# Hexapod_REV1.net
KiCad netlist of a schematic drawn in EAGLE
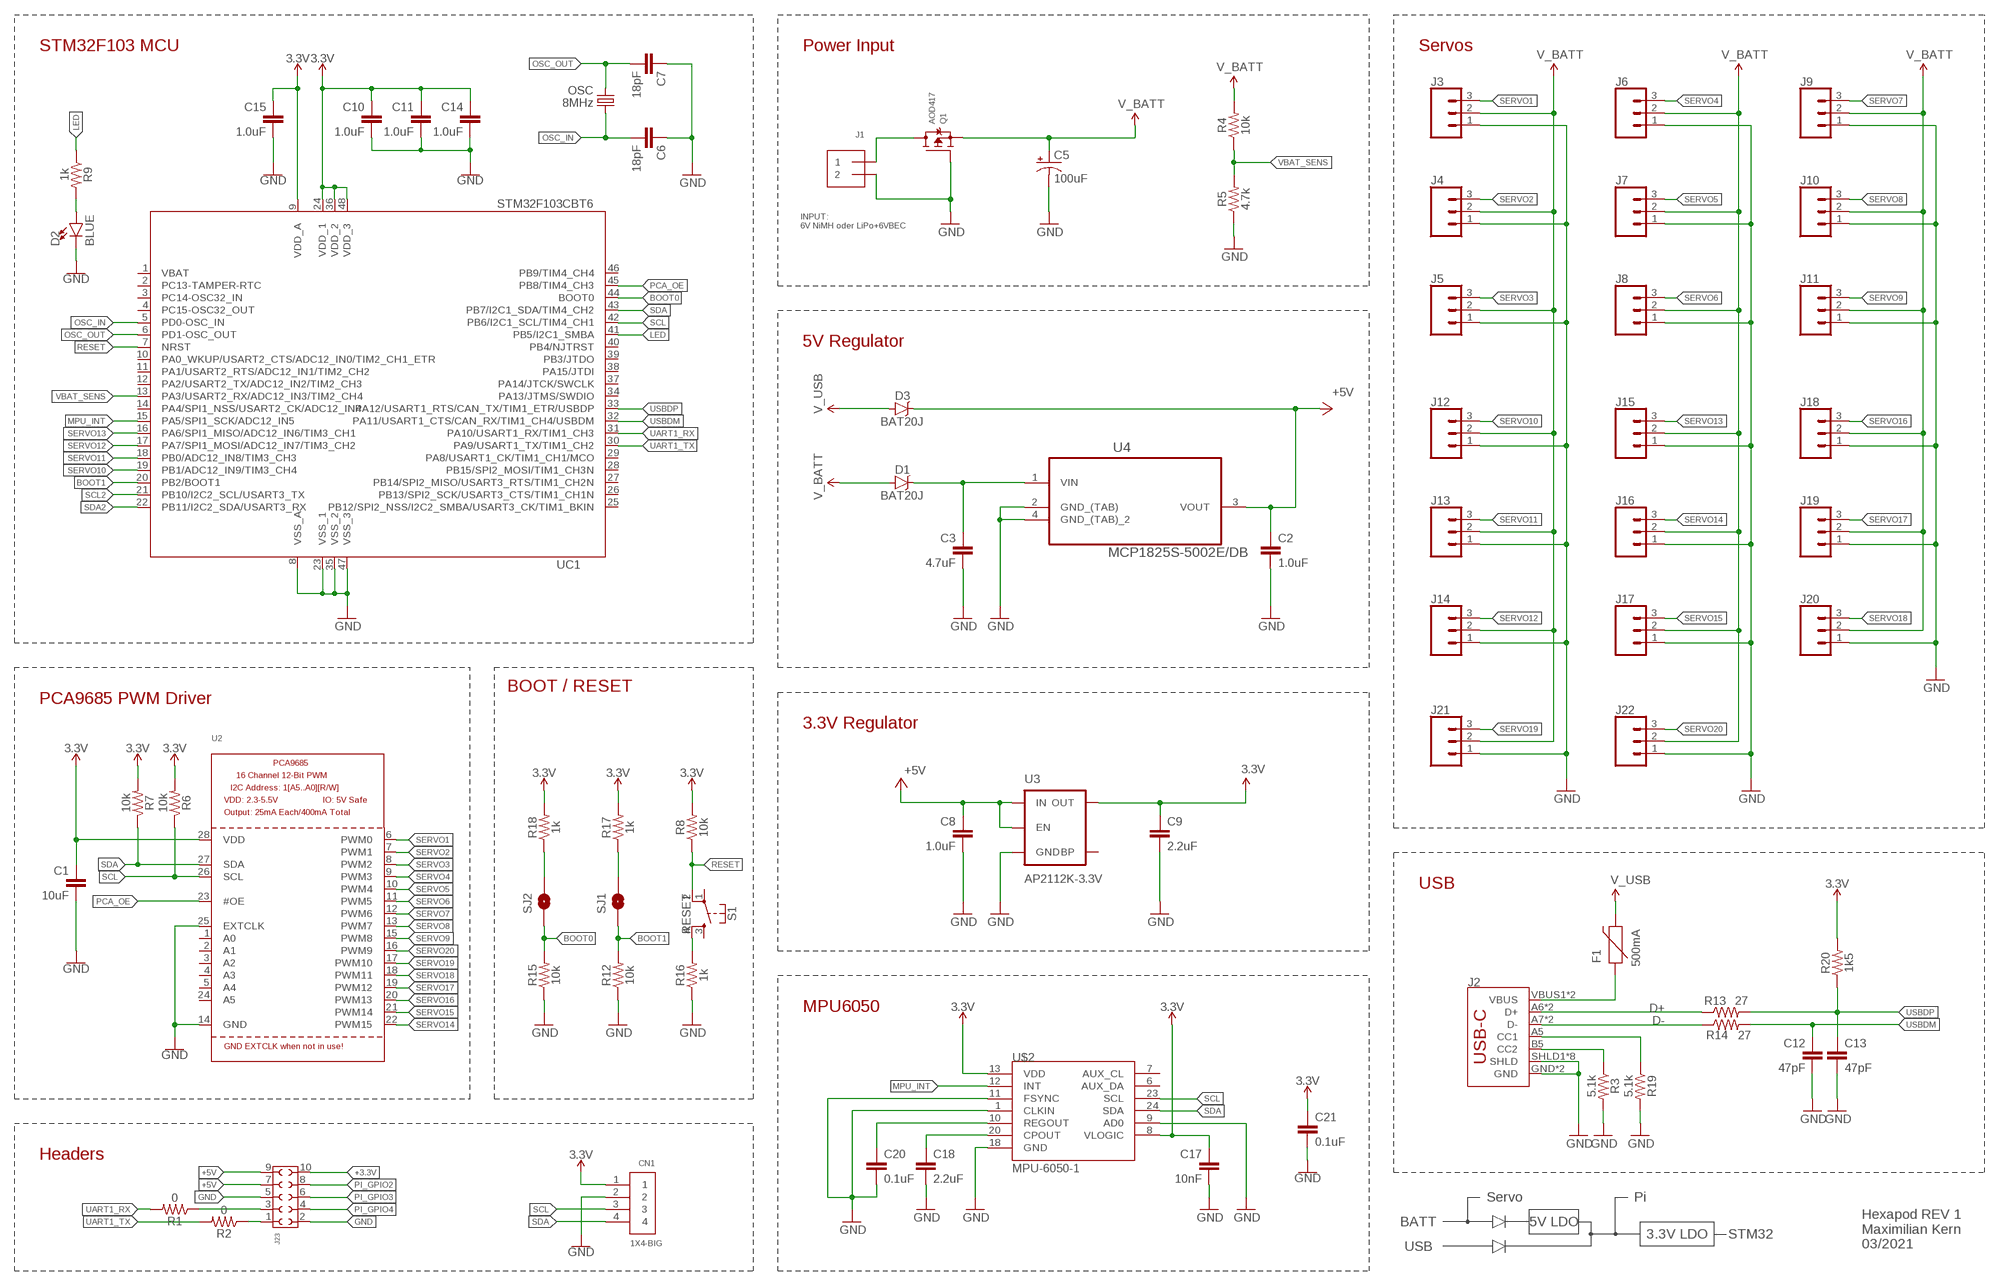
[diagram p0: schematic, sheet 1]

(export (version "E")
  (design (tool "Eeschema 10.0.6"))
  (components
    (comp (ref "C1")
      (value "10uF")
      (footprint "eagle-import:0805")
      (libsource (lib "eagle-import") (part "1.0UF-0805-25V-(+80/-20%)"))
    )
    (comp (ref "C2")
      (value "1.0uF")
      (footprint "eagle-import:0805")
      (libsource (lib "eagle-import") (part "1.0UF-0805-25V-(+80/-20%)"))
    )
    (comp (ref "C3")
      (value "4.7uF")
      (footprint "eagle-import:0805")
      (libsource (lib "eagle-import") (part "1.0UF-0805-25V-(+80/-20%)"))
    )
    (comp (ref "C5")
      (value "100uF")
      (footprint "eagle-import:PANASONIC_D")
      (libsource (lib "eagle-import") (part "100UF-POLAR-25V-20%(ELEC)"))
    )
    (comp (ref "C6")
      (value "18pF")
      (footprint "eagle-import:0603")
      (libsource (lib "eagle-import") (part "47PF-0603-50V-5%"))
    )
    (comp (ref "C7")
      (value "18pF")
      (footprint "eagle-import:0603")
      (libsource (lib "eagle-import") (part "47PF-0603-50V-5%"))
    )
    (comp (ref "C8")
      (value "1.0uF")
      (footprint "eagle-import:0805")
      (libsource (lib "eagle-import") (part "1.0UF-0805-25V-(+80/-20%)"))
    )
    (comp (ref "C9")
      (value "2.2uF")
      (footprint "eagle-import:0805")
      (libsource (lib "eagle-import") (part "1.0UF-0805-25V-(+80/-20%)"))
    )
    (comp (ref "C10")
      (value "1.0uF")
      (footprint "eagle-import:0805")
      (libsource (lib "eagle-import") (part "1.0UF-0805-25V-(+80/-20%)"))
    )
    (comp (ref "C11")
      (value "1.0uF")
      (footprint "eagle-import:0805")
      (libsource (lib "eagle-import") (part "1.0UF-0805-25V-(+80/-20%)"))
    )
    (comp (ref "C12")
      (value "47pF")
      (footprint "eagle-import:0603")
      (libsource (lib "eagle-import") (part "47PF-0603-50V-5%"))
    )
    (comp (ref "C13")
      (value "47pF")
      (footprint "eagle-import:0603")
      (libsource (lib "eagle-import") (part "47PF-0603-50V-5%"))
    )
    (comp (ref "C14")
      (value "1.0uF")
      (footprint "eagle-import:0805")
      (libsource (lib "eagle-import") (part "1.0UF-0805-25V-(+80/-20%)"))
    )
    (comp (ref "C15")
      (value "1.0uF")
      (footprint "eagle-import:0805")
      (libsource (lib "eagle-import") (part "1.0UF-0805-25V-(+80/-20%)"))
    )
    (comp (ref "C17")
      (value "10nF")
      (footprint "eagle-import:0603")
      (libsource (lib "eagle-import") (part "47PF-0603-50V-5%"))
    )
    (comp (ref "C18")
      (value "2.2uF")
      (footprint "eagle-import:0805")
      (libsource (lib "eagle-import") (part "1.0UF-0805-25V-(+80/-20%)"))
    )
    (comp (ref "C20")
      (value "0.1uF")
      (footprint "eagle-import:0603")
      (libsource (lib "eagle-import") (part "0.1UF-0603-25V-(+80/-20%)"))
    )
    (comp (ref "C21")
      (value "0.1uF")
      (footprint "eagle-import:0603")
      (libsource (lib "eagle-import") (part "0.1UF-0603-25V-(+80/-20%)"))
    )
    (comp (ref "CN1")
      (value "1X4-BIG")
      (footprint "eagle-import:1X04-BIG")
      (libsource (lib "eagle-import") (part "1X4-BIG"))
    )
    (comp (ref "D1")
      (value "BAT20J")
      (footprint "eagle-import:SOD-323")
      (libsource (lib "eagle-import") (part "DIODE-SCHOTTKY-BAT20J"))
    )
    (comp (ref "D2")
      (value "BLUE")
      (footprint "eagle-import:LED-0603@2")
      (libsource (lib "eagle-import") (part "LED-BLUE0603"))
    )
    (comp (ref "D3")
      (value "BAT20J")
      (footprint "eagle-import:SOD-323")
      (libsource (lib "eagle-import") (part "DIODE-SCHOTTKY-BAT20J"))
    )
    (comp (ref "F1")
      (value "500mA")
      (footprint "eagle-import:PTC-1206")
      (libsource (lib "eagle-import") (part "PTCSMD"))
    )
    (comp (ref "J1")
      (value "TERMBLOCK_1X2")
      (footprint "eagle-import:TERMBLOCK_1X2-3.5MM")
      (libsource (lib "eagle-import") (part "TERMBLOCK_1X2"))
    )
    (comp (ref "J2")
      (value "USB_C16PIN")
      (footprint "eagle-import:USB-C-16P")
      (libsource (lib "eagle-import") (part "USB_C16PIN"))
    )
    (comp (ref "J3")
      (value "CONN_03")
      (footprint "eagle-import:1X03")
      (libsource (lib "eagle-import") (part "CONN_03"))
    )
    (comp (ref "J4")
      (value "CONN_03")
      (footprint "eagle-import:1X03")
      (libsource (lib "eagle-import") (part "CONN_03"))
    )
    (comp (ref "J5")
      (value "CONN_03")
      (footprint "eagle-import:1X03")
      (libsource (lib "eagle-import") (part "CONN_03"))
    )
    (comp (ref "J6")
      (value "CONN_03")
      (footprint "eagle-import:1X03")
      (libsource (lib "eagle-import") (part "CONN_03"))
    )
    (comp (ref "J7")
      (value "CONN_03")
      (footprint "eagle-import:1X03")
      (libsource (lib "eagle-import") (part "CONN_03"))
    )
    (comp (ref "J8")
      (value "CONN_03")
      (footprint "eagle-import:1X03")
      (libsource (lib "eagle-import") (part "CONN_03"))
    )
    (comp (ref "J9")
      (value "CONN_03")
      (footprint "eagle-import:1X03")
      (libsource (lib "eagle-import") (part "CONN_03"))
    )
    (comp (ref "J10")
      (value "CONN_03")
      (footprint "eagle-import:1X03")
      (libsource (lib "eagle-import") (part "CONN_03"))
    )
    (comp (ref "J11")
      (value "CONN_03")
      (footprint "eagle-import:1X03")
      (libsource (lib "eagle-import") (part "CONN_03"))
    )
    (comp (ref "J12")
      (value "CONN_03")
      (footprint "eagle-import:1X03")
      (libsource (lib "eagle-import") (part "CONN_03"))
    )
    (comp (ref "J13")
      (value "CONN_03")
      (footprint "eagle-import:1X03")
      (libsource (lib "eagle-import") (part "CONN_03"))
    )
    (comp (ref "J14")
      (value "CONN_03")
      (footprint "eagle-import:1X03")
      (libsource (lib "eagle-import") (part "CONN_03"))
    )
    (comp (ref "J15")
      (value "CONN_03")
      (footprint "eagle-import:1X03")
      (libsource (lib "eagle-import") (part "CONN_03"))
    )
    (comp (ref "J16")
      (value "CONN_03")
      (footprint "eagle-import:1X03")
      (libsource (lib "eagle-import") (part "CONN_03"))
    )
    (comp (ref "J17")
      (value "CONN_03")
      (footprint "eagle-import:1X03")
      (libsource (lib "eagle-import") (part "CONN_03"))
    )
    (comp (ref "J18")
      (value "CONN_03")
      (footprint "eagle-import:1X03")
      (libsource (lib "eagle-import") (part "CONN_03"))
    )
    (comp (ref "J19")
      (value "CONN_03")
      (footprint "eagle-import:1X03")
      (libsource (lib "eagle-import") (part "CONN_03"))
    )
    (comp (ref "J20")
      (value "CONN_03")
      (footprint "eagle-import:1X03")
      (libsource (lib "eagle-import") (part "CONN_03"))
    )
    (comp (ref "J21")
      (value "CONN_03")
      (footprint "eagle-import:1X03")
      (libsource (lib "eagle-import") (part "CONN_03"))
    )
    (comp (ref "J22")
      (value "CONN_03")
      (footprint "eagle-import:1X03")
      (libsource (lib "eagle-import") (part "CONN_03"))
    )
    (comp (ref "J23")
      (value "6103XX21821_61031021821")
      (footprint "eagle-import:61031021821")
      (libsource (lib "eagle-import") (part "6103XX21821_61031021821"))
    )
    (comp (ref "OSC")
      (value "8MHz")
      (footprint "eagle-import:CRYSTAL-SMD-5X3")
      (libsource (lib "eagle-import") (part "CRYSTAL5X3"))
    )
    (comp (ref "Q1")
      (value "AOD417")
      (footprint "eagle-import:TO252")
      (libsource (lib "eagle-import") (part "MOSFET-PTO252"))
    )
    (comp (ref "R1")
      (value "0")
      (footprint "eagle-import:0603")
      (libsource (lib "eagle-import") (part "10KOHM-0603-1/10W-1%"))
    )
    (comp (ref "R2")
      (value "0")
      (footprint "eagle-import:0603")
      (libsource (lib "eagle-import") (part "10KOHM-0603-1/10W-1%"))
    )
    (comp (ref "R3")
      (value "5.1k")
      (footprint "eagle-import:0603")
      (libsource (lib "eagle-import") (part "10KOHM-0603-1/10W-1%"))
    )
    (comp (ref "R4")
      (value "10k")
      (footprint "eagle-import:0603")
      (libsource (lib "eagle-import") (part "10KOHM-0603-1/10W-1%"))
    )
    (comp (ref "R5")
      (value "4.7k")
      (footprint "eagle-import:0603")
      (libsource (lib "eagle-import") (part "10KOHM-0603-1/10W-1%"))
    )
    (comp (ref "R6")
      (value "10k")
      (footprint "eagle-import:0603")
      (libsource (lib "eagle-import") (part "10KOHM-0603-1/10W-1%"))
    )
    (comp (ref "R7")
      (value "10k")
      (footprint "eagle-import:0603")
      (libsource (lib "eagle-import") (part "10KOHM-0603-1/10W-1%"))
    )
    (comp (ref "R8")
      (value "10k")
      (footprint "eagle-import:0603")
      (libsource (lib "eagle-import") (part "10KOHM-0603-1/10W-1%"))
    )
    (comp (ref "R9")
      (value "1k")
      (footprint "eagle-import:0603")
      (libsource (lib "eagle-import") (part "1KOHM-0603-1/10W-1%"))
    )
    (comp (ref "R12")
      (value "10k")
      (footprint "eagle-import:0603")
      (libsource (lib "eagle-import") (part "10KOHM-0603-1/10W-1%"))
    )
    (comp (ref "R13")
      (value "27")
      (footprint "eagle-import:0603")
      (libsource (lib "eagle-import") (part "27OHM1/10W1%(0603)0603-RES"))
    )
    (comp (ref "R14")
      (value "27")
      (footprint "eagle-import:0603")
      (libsource (lib "eagle-import") (part "27OHM1/10W1%(0603)0603-RES"))
    )
    (comp (ref "R15")
      (value "10k")
      (footprint "eagle-import:0603")
      (libsource (lib "eagle-import") (part "10KOHM-0603-1/10W-1%"))
    )
    (comp (ref "R16")
      (value "1k")
      (footprint "eagle-import:0603")
      (libsource (lib "eagle-import") (part "10KOHM-0603-1/10W-1%"))
    )
    (comp (ref "R17")
      (value "1k")
      (footprint "eagle-import:0603")
      (libsource (lib "eagle-import") (part "10KOHM-0603-1/10W-1%"))
    )
    (comp (ref "R18")
      (value "1k")
      (footprint "eagle-import:0603")
      (libsource (lib "eagle-import") (part "10KOHM-0603-1/10W-1%"))
    )
    (comp (ref "R19")
      (value "5.1k")
      (footprint "eagle-import:0603")
      (libsource (lib "eagle-import") (part "10KOHM-0603-1/10W-1%"))
    )
    (comp (ref "R20")
      (value "1k5")
      (footprint "eagle-import:0603")
      (libsource (lib "eagle-import") (part "10KOHM-0603-1/10W-1%"))
    )
    (comp (ref "S1")
      (value "RESET")
      (footprint "eagle-import:TACTILE_SWITCH_SMD_4.6X2.8MM")
      (libsource (lib "eagle-import") (part "MOMENTARY-SWITCH-SPST-2-SMD-4.6X2.8MM"))
    )
    (comp (ref "SJ1")
      (value "JUMPER-PAD-2-NOYES_SILK")
      (footprint "eagle-import:PAD-JUMPER-2-NO_YES_SILK")
      (libsource (lib "eagle-import") (part "JUMPER-PAD-2-NOYES_SILK"))
    )
    (comp (ref "SJ2")
      (value "JUMPER-PAD-2-NOYES_SILK")
      (footprint "eagle-import:PAD-JUMPER-2-NO_YES_SILK")
      (libsource (lib "eagle-import") (part "JUMPER-PAD-2-NOYES_SILK"))
    )
    (comp (ref "U$2")
      (value "MPU-6050-1")
      (footprint "eagle-import:QFN-24-4MM2")
      (libsource (lib "eagle-import") (part "MPU-6050-1"))
    )
    (comp (ref "U2")
      (value "PCA9685")
      (footprint "eagle-import:TSSOP28")
      (libsource (lib "eagle-import") (part "PCA9685"))
    )
    (comp (ref "U3")
      (value "AP2112K-3.3V")
      (footprint "eagle-import:SOT23-5")
      (libsource (lib "eagle-import") (part "V_REG_LDOSMD"))
    )
    (comp (ref "U4")
      (value "MCP1825S-5002E/DB")
      (footprint "eagle-import:SOT230P700X180-4N")
      (libsource (lib "eagle-import") (part "MCP1825S-5002E/DB"))
    )
    (comp (ref "UC1")
      (value "STM32F103CBT6")
      (footprint "eagle-import:LQFP48")
      (libsource (lib "eagle-import") (part "STM32F103CB"))
    )
  )
  (nets
    (net (code "1") (name "+3.3V") (class "Default")
      (node (ref "J23") (pin "10") (pinfunction "10_10") (pintype "passive"))
    )
    (net (code "2") (name "+5V") (class "Default")
      (node (ref "C2") (pin "1") (pinfunction "1_1") (pintype "passive"))
      (node (ref "C8") (pin "1") (pinfunction "1_1") (pintype "passive"))
      (node (ref "D3") (pin "C") (pinfunction "C_C") (pintype "passive"))
      (node (ref "J23") (pin "7") (pinfunction "7_7") (pintype "passive"))
      (node (ref "J23") (pin "9") (pinfunction "9_9") (pintype "passive"))
      (node (ref "U3") (pin "1") (pinfunction "IN_1") (pintype "input"))
      (node (ref "U3") (pin "3") (pinfunction "EN_3") (pintype "input"))
      (node (ref "U4") (pin "3") (pinfunction "VOUT_3") (pintype "output"))
    )
    (net (code "3") (name "/D+") (class "Default")
      (node (ref "J2") (pin "A6") (pinfunction "D+_A6") (pintype "bidirectional"))
      (node (ref "J2") (pin "B6") (pinfunction "D+_B6") (pintype "bidirectional"))
      (node (ref "R13") (pin "1") (pinfunction "1_1") (pintype "passive"))
    )
    (net (code "4") (name "/D-") (class "Default")
      (node (ref "J2") (pin "A7") (pinfunction "D-_A7") (pintype "bidirectional"))
      (node (ref "J2") (pin "B7") (pinfunction "D-_B7") (pintype "bidirectional"))
      (node (ref "R14") (pin "1") (pinfunction "1_1") (pintype "passive"))
    )
    (net (code "5") (name "/PI_TXD") (class "Default")
      (node (ref "J23") (pin "3") (pinfunction "3_3") (pintype "passive"))
      (node (ref "R1") (pin "1") (pinfunction "1_1") (pintype "passive"))
    )
    (net (code "6") (name "/VBAT") (class "Default")
      (node (ref "UC1") (pin "1") (pinfunction "VBAT_1") (pintype "power_in"))
    )
    (net (code "7") (name "3.3V") (class "Default")
      (node (ref "C1") (pin "1") (pinfunction "1_1") (pintype "passive"))
      (node (ref "C10") (pin "1") (pinfunction "1_1") (pintype "passive"))
      (node (ref "C11") (pin "1") (pinfunction "1_1") (pintype "passive"))
      (node (ref "C14") (pin "1") (pinfunction "1_1") (pintype "passive"))
      (node (ref "C15") (pin "1") (pinfunction "1_1") (pintype "passive"))
      (node (ref "C17") (pin "1") (pinfunction "1_1") (pintype "passive"))
      (node (ref "C21") (pin "1") (pinfunction "1_1") (pintype "passive"))
      (node (ref "C9") (pin "1") (pinfunction "1_1") (pintype "passive"))
      (node (ref "CN1") (pin "1") (pinfunction "1_1") (pintype "bidirectional"))
      (node (ref "R17") (pin "2") (pinfunction "2_2") (pintype "passive"))
      (node (ref "R18") (pin "2") (pinfunction "2_2") (pintype "passive"))
      (node (ref "R20") (pin "2") (pinfunction "2_2") (pintype "passive"))
      (node (ref "R6") (pin "2") (pinfunction "2_2") (pintype "passive"))
      (node (ref "R7") (pin "2") (pinfunction "2_2") (pintype "passive"))
      (node (ref "R8") (pin "2") (pinfunction "2_2") (pintype "passive"))
      (node (ref "U$2") (pin "13") (pinfunction "VDD_13") (pintype "bidirectional"))
      (node (ref "U$2") (pin "8") (pinfunction "VLOGIC_8") (pintype "bidirectional"))
      (node (ref "U2") (pin "28") (pinfunction "VDD_28") (pintype "power_in"))
      (node (ref "U3") (pin "5") (pinfunction "OUT_5") (pintype "passive"))
      (node (ref "UC1") (pin "24") (pinfunction "VDD_1_24") (pintype "power_in"))
      (node (ref "UC1") (pin "36") (pinfunction "VDD_2_36") (pintype "power_in"))
      (node (ref "UC1") (pin "48") (pinfunction "VDD_3_48") (pintype "power_in"))
      (node (ref "UC1") (pin "9") (pinfunction "VDD_A_9") (pintype "power_in"))
    )
    (net (code "8") (name "BOOT0") (class "Default")
      (node (ref "R15") (pin "2") (pinfunction "2_2") (pintype "passive"))
      (node (ref "SJ2") (pin "1") (pinfunction "1_1") (pintype "passive"))
      (node (ref "UC1") (pin "44") (pinfunction "BOOT0_44") (pintype "input"))
    )
    (net (code "9") (name "BOOT1") (class "Default")
      (node (ref "R12") (pin "2") (pinfunction "2_2") (pintype "passive"))
      (node (ref "SJ1") (pin "1") (pinfunction "1_1") (pintype "passive"))
      (node (ref "UC1") (pin "20") (pinfunction "PB2/BOOT1_20") (pintype "bidirectional"))
    )
    (net (code "10") (name "GND") (class "Default")
      (node (ref "C1") (pin "2") (pinfunction "2_2") (pintype "passive"))
      (node (ref "C10") (pin "2") (pinfunction "2_2") (pintype "passive"))
      (node (ref "C11") (pin "2") (pinfunction "2_2") (pintype "passive"))
      (node (ref "C12") (pin "2") (pinfunction "2_2") (pintype "passive"))
      (node (ref "C13") (pin "2") (pinfunction "2_2") (pintype "passive"))
      (node (ref "C14") (pin "2") (pinfunction "2_2") (pintype "passive"))
      (node (ref "C15") (pin "2") (pinfunction "2_2") (pintype "passive"))
      (node (ref "C17") (pin "2") (pinfunction "2_2") (pintype "passive"))
      (node (ref "C18") (pin "2") (pinfunction "2_2") (pintype "passive"))
      (node (ref "C2") (pin "2") (pinfunction "2_2") (pintype "passive"))
      (node (ref "C20") (pin "2") (pinfunction "2_2") (pintype "passive"))
      (node (ref "C21") (pin "2") (pinfunction "2_2") (pintype "passive"))
      (node (ref "C3") (pin "2") (pinfunction "2_2") (pintype "passive"))
      (node (ref "C5") (pin "-") (pinfunction "-_-") (pintype "passive"))
      (node (ref "C6") (pin "1") (pinfunction "1_1") (pintype "passive"))
      (node (ref "C7") (pin "1") (pinfunction "1_1") (pintype "passive"))
      (node (ref "C8") (pin "2") (pinfunction "2_2") (pintype "passive"))
      (node (ref "C9") (pin "2") (pinfunction "2_2") (pintype "passive"))
      (node (ref "CN1") (pin "2") (pinfunction "2_2") (pintype "bidirectional"))
      (node (ref "D2") (pin "C") (pinfunction "C_C") (pintype "passive"))
      (node (ref "J1") (pin "2") (pinfunction "2_2") (pintype "passive"))
      (node (ref "J10") (pin "1") (pinfunction "1_1") (pintype "passive"))
      (node (ref "J11") (pin "1") (pinfunction "1_1") (pintype "passive"))
      (node (ref "J12") (pin "1") (pinfunction "1_1") (pintype "passive"))
      (node (ref "J13") (pin "1") (pinfunction "1_1") (pintype "passive"))
      (node (ref "J14") (pin "1") (pinfunction "1_1") (pintype "passive"))
      (node (ref "J15") (pin "1") (pinfunction "1_1") (pintype "passive"))
      (node (ref "J16") (pin "1") (pinfunction "1_1") (pintype "passive"))
      (node (ref "J17") (pin "1") (pinfunction "1_1") (pintype "passive"))
      (node (ref "J18") (pin "1") (pinfunction "1_1") (pintype "passive"))
      (node (ref "J19") (pin "1") (pinfunction "1_1") (pintype "passive"))
      (node (ref "J2") (pin "GND") (pinfunction "GND_GND") (pintype "bidirectional"))
      (node (ref "J2") (pin "GND2") (pinfunction "GND_GND2") (pintype "bidirectional"))
      (node (ref "J2") (pin "SHLD1") (pinfunction "SHLD_SHLD1") (pintype "bidirectional"))
      (node (ref "J2") (pin "SHLD2") (pinfunction "SHLD_SHLD2") (pintype "bidirectional"))
      (node (ref "J2") (pin "SHLD3") (pinfunction "SHLD_SHLD3") (pintype "bidirectional"))
      (node (ref "J2") (pin "SHLD4") (pinfunction "SHLD_SHLD4") (pintype "bidirectional"))
      (node (ref "J2") (pin "SHLD5") (pinfunction "SHLD_SHLD5") (pintype "bidirectional"))
      (node (ref "J2") (pin "SHLD6") (pinfunction "SHLD_SHLD6") (pintype "bidirectional"))
      (node (ref "J2") (pin "SHLD7") (pinfunction "SHLD_SHLD7") (pintype "bidirectional"))
      (node (ref "J2") (pin "SHLD8") (pinfunction "SHLD_SHLD8") (pintype "bidirectional"))
      (node (ref "J20") (pin "1") (pinfunction "1_1") (pintype "passive"))
      (node (ref "J21") (pin "1") (pinfunction "1_1") (pintype "passive"))
      (node (ref "J22") (pin "1") (pinfunction "1_1") (pintype "passive"))
      (node (ref "J23") (pin "2") (pinfunction "2_2") (pintype "passive"))
      (node (ref "J23") (pin "5") (pinfunction "5_5") (pintype "passive"))
      (node (ref "J3") (pin "1") (pinfunction "1_1") (pintype "passive"))
      (node (ref "J4") (pin "1") (pinfunction "1_1") (pintype "passive"))
      (node (ref "J5") (pin "1") (pinfunction "1_1") (pintype "passive"))
      (node (ref "J6") (pin "1") (pinfunction "1_1") (pintype "passive"))
      (node (ref "J7") (pin "1") (pinfunction "1_1") (pintype "passive"))
      (node (ref "J8") (pin "1") (pinfunction "1_1") (pintype "passive"))
      (node (ref "J9") (pin "1") (pinfunction "1_1") (pintype "passive"))
      (node (ref "Q1") (pin "1") (pinfunction "G_1") (pintype "passive"))
      (node (ref "R12") (pin "1") (pinfunction "1_1") (pintype "passive"))
      (node (ref "R15") (pin "1") (pinfunction "1_1") (pintype "passive"))
      (node (ref "R16") (pin "1") (pinfunction "1_1") (pintype "passive"))
      (node (ref "R19") (pin "2") (pinfunction "2_2") (pintype "passive"))
      (node (ref "R3") (pin "2") (pinfunction "2_2") (pintype "passive"))
      (node (ref "R5") (pin "1") (pinfunction "1_1") (pintype "passive"))
      (node (ref "U$2") (pin "1") (pinfunction "CLKIN_1") (pintype "bidirectional"))
      (node (ref "U$2") (pin "11") (pinfunction "FSYNC_11") (pintype "bidirectional"))
      (node (ref "U$2") (pin "18") (pinfunction "GND_18") (pintype "bidirectional"))
      (node (ref "U$2") (pin "9") (pinfunction "AD0_9") (pintype "bidirectional"))
      (node (ref "U2") (pin "14") (pinfunction "GND_14") (pintype "power_in"))
      (node (ref "U2") (pin "25") (pinfunction "EXTCLK_25") (pintype "input"))
      (node (ref "U3") (pin "2") (pinfunction "GND_2") (pintype "input"))
      (node (ref "U4") (pin "2") (pinfunction "GND_(TAB)_2") (pintype "passive"))
      (node (ref "U4") (pin "4") (pinfunction "GND_(TAB)_2_4") (pintype "passive"))
      (node (ref "UC1") (pin "23") (pinfunction "VSS_1_23") (pintype "power_in"))
      (node (ref "UC1") (pin "35") (pinfunction "VSS_2_35") (pintype "power_in"))
      (node (ref "UC1") (pin "47") (pinfunction "VSS_3_47") (pintype "power_in"))
      (node (ref "UC1") (pin "8") (pinfunction "VSS_A_8") (pintype "power_in"))
    )
    (net (code "11") (name "LED") (class "Default")
      (node (ref "R9") (pin "1") (pinfunction "1_1") (pintype "passive"))
      (node (ref "UC1") (pin "41") (pinfunction "PB5/I2C1_SMBA_41") (pintype "input"))
    )
    (net (code "12") (name "MPU_INT") (class "Default")
      (node (ref "U$2") (pin "12") (pinfunction "INT_12") (pintype "bidirectional"))
      (node (ref "UC1") (pin "15") (pinfunction "PA5/SPI1_SCK/ADC12_IN5_15") (pintype "bidirectional"))
    )
    (net (code "13") (name "Net-(D2-PadA)") (class "Default")
      (node (ref "D2") (pin "A") (pinfunction "A_A") (pintype "passive"))
      (node (ref "R9") (pin "2") (pinfunction "2_2") (pintype "passive"))
    )
    (net (code "14") (name "Net-(F1-Pad1)") (class "Default")
      (node (ref "F1") (pin "1") (pinfunction "1_1") (pintype "bidirectional"))
      (node (ref "J2") (pin "VBUS1") (pinfunction "VBUS_VBUS1") (pintype "bidirectional"))
      (node (ref "J2") (pin "VBUS2") (pinfunction "VBUS_VBUS2") (pintype "bidirectional"))
    )
    (net (code "15") (name "Net-(J2-CC1)") (class "Default")
      (node (ref "J2") (pin "A5") (pinfunction "CC1_A5") (pintype "bidirectional"))
      (node (ref "R19") (pin "1") (pinfunction "1_1") (pintype "passive"))
    )
    (net (code "16") (name "Net-(J2-CC2)") (class "Default")
      (node (ref "J2") (pin "B5") (pinfunction "CC2_B5") (pintype "bidirectional"))
      (node (ref "R3") (pin "1") (pinfunction "1_1") (pintype "passive"))
    )
    (net (code "17") (name "Net-(J23-Pad1)") (class "Default")
      (node (ref "J23") (pin "1") (pinfunction "1_1") (pintype "passive"))
      (node (ref "R2") (pin "1") (pinfunction "1_1") (pintype "passive"))
    )
    (net (code "18") (name "Net-(Q1-D)") (class "Default")
      (node (ref "J1") (pin "1") (pinfunction "1_1") (pintype "passive"))
      (node (ref "Q1") (pin "3") (pinfunction "D_3") (pintype "passive"))
    )
    (net (code "19") (name "Net-(R16-Pad2)") (class "Default")
      (node (ref "R16") (pin "2") (pinfunction "2_2") (pintype "passive"))
      (node (ref "S1") (pin "4") (pinfunction "4_4") (pintype "passive"))
    )
    (net (code "20") (name "Net-(R17-Pad1)") (class "Default")
      (node (ref "R17") (pin "1") (pinfunction "1_1") (pintype "passive"))
      (node (ref "SJ1") (pin "2") (pinfunction "2_2") (pintype "passive"))
    )
    (net (code "21") (name "Net-(R18-Pad1)") (class "Default")
      (node (ref "R18") (pin "1") (pinfunction "1_1") (pintype "passive"))
      (node (ref "SJ2") (pin "2") (pinfunction "2_2") (pintype "passive"))
    )
    (net (code "22") (name "Net-(U$2-CPOUT)") (class "Default")
      (node (ref "C18") (pin "1") (pinfunction "1_1") (pintype "passive"))
      (node (ref "U$2") (pin "20") (pinfunction "CPOUT_20") (pintype "bidirectional"))
    )
    (net (code "23") (name "Net-(U$2-REGOUT)") (class "Default")
      (node (ref "C20") (pin "1") (pinfunction "1_1") (pintype "passive"))
      (node (ref "U$2") (pin "10") (pinfunction "REGOUT_10") (pintype "bidirectional"))
    )
    (net (code "24") (name "Net-(U4-VIN)") (class "Default")
      (node (ref "C3") (pin "1") (pinfunction "1_1") (pintype "passive"))
      (node (ref "D1") (pin "C") (pinfunction "C_C") (pintype "passive"))
      (node (ref "U4") (pin "1") (pinfunction "VIN_1") (pintype "input"))
    )
    (net (code "25") (name "OSC_IN") (class "Default")
      (node (ref "C6") (pin "2") (pinfunction "2_2") (pintype "passive"))
      (node (ref "OSC") (pin "1") (pinfunction "1_1") (pintype "passive"))
      (node (ref "UC1") (pin "5") (pinfunction "PD0-OSC_IN_5") (pintype "input"))
    )
    (net (code "26") (name "OSC_OUT") (class "Default")
      (node (ref "C7") (pin "2") (pinfunction "2_2") (pintype "passive"))
      (node (ref "OSC") (pin "3") (pinfunction "2_3") (pintype "passive"))
      (node (ref "UC1") (pin "6") (pinfunction "PD1-OSC_OUT_6") (pintype "input"))
    )
    (net (code "27") (name "PCA_OE") (class "Default")
      (node (ref "U2") (pin "23") (pinfunction "#OE_23") (pintype "input"))
      (node (ref "UC1") (pin "45") (pinfunction "PB8/TIM4_CH3_45") (pintype "bidirectional"))
    )
    (net (code "28") (name "PI_GPIO2") (class "Default")
      (node (ref "J23") (pin "8") (pinfunction "8_8") (pintype "passive"))
    )
    (net (code "29") (name "PI_GPIO3") (class "Default")
      (node (ref "J23") (pin "6") (pinfunction "6_6") (pintype "passive"))
    )
    (net (code "30") (name "PI_GPIO4") (class "Default")
      (node (ref "J23") (pin "4") (pinfunction "4_4") (pintype "passive"))
    )
    (net (code "31") (name "RESET") (class "Default")
      (node (ref "R8") (pin "1") (pinfunction "1_1") (pintype "passive"))
      (node (ref "S1") (pin "2") (pinfunction "2_2") (pintype "passive"))
      (node (ref "UC1") (pin "7") (pinfunction "NRST_7") (pintype "input"))
    )
    (net (code "32") (name "SCL") (class "Default")
      (node (ref "CN1") (pin "3") (pinfunction "3_3") (pintype "bidirectional"))
      (node (ref "R6") (pin "1") (pinfunction "1_1") (pintype "passive"))
      (node (ref "U$2") (pin "23") (pinfunction "SCL_23") (pintype "bidirectional"))
      (node (ref "U2") (pin "26") (pinfunction "SCL_26") (pintype "bidirectional"))
      (node (ref "UC1") (pin "42") (pinfunction "PB6/I2C1_SCL/TIM4_CH1_42") (pintype "input"))
    )
    (net (code "33") (name "SCL2") (class "Default")
      (node (ref "UC1") (pin "21") (pinfunction "PB10/I2C2_SCL/USART3_TX_21") (pintype "input"))
    )
    (net (code "34") (name "SDA") (class "Default")
      (node (ref "CN1") (pin "4") (pinfunction "4_4") (pintype "bidirectional"))
      (node (ref "R7") (pin "1") (pinfunction "1_1") (pintype "passive"))
      (node (ref "U$2") (pin "24") (pinfunction "SDA_24") (pintype "bidirectional"))
      (node (ref "U2") (pin "27") (pinfunction "SDA_27") (pintype "bidirectional"))
      (node (ref "UC1") (pin "43") (pinfunction "PB7/I2C1_SDA/TIM4_CH2_43") (pintype "bidirectional"))
    )
    (net (code "35") (name "SDA2") (class "Default")
      (node (ref "UC1") (pin "22") (pinfunction "PB11/I2C2_SDA/USART3_RX_22") (pintype "input"))
    )
    (net (code "36") (name "SERVO1") (class "Default")
      (node (ref "J3") (pin "3") (pinfunction "3_3") (pintype "passive"))
      (node (ref "U2") (pin "6") (pinfunction "PWM0_6") (pintype "output"))
    )
    (net (code "37") (name "SERVO2") (class "Default")
      (node (ref "J4") (pin "3") (pinfunction "3_3") (pintype "passive"))
      (node (ref "U2") (pin "7") (pinfunction "PWM1_7") (pintype "output"))
    )
    (net (code "38") (name "SERVO3") (class "Default")
      (node (ref "J5") (pin "3") (pinfunction "3_3") (pintype "passive"))
      (node (ref "U2") (pin "8") (pinfunction "PWM2_8") (pintype "output"))
    )
    (net (code "39") (name "SERVO4") (class "Default")
      (node (ref "J6") (pin "3") (pinfunction "3_3") (pintype "passive"))
      (node (ref "U2") (pin "9") (pinfunction "PWM3_9") (pintype "output"))
    )
    (net (code "40") (name "SERVO5") (class "Default")
      (node (ref "J7") (pin "3") (pinfunction "3_3") (pintype "passive"))
      (node (ref "U2") (pin "10") (pinfunction "PWM4_10") (pintype "output"))
    )
    (net (code "41") (name "SERVO6") (class "Default")
      (node (ref "J8") (pin "3") (pinfunction "3_3") (pintype "passive"))
      (node (ref "U2") (pin "11") (pinfunction "PWM5_11") (pintype "output"))
    )
    (net (code "42") (name "SERVO7") (class "Default")
      (node (ref "J9") (pin "3") (pinfunction "3_3") (pintype "passive"))
      (node (ref "U2") (pin "12") (pinfunction "PWM6_12") (pintype "output"))
    )
    (net (code "43") (name "SERVO8") (class "Default")
      (node (ref "J10") (pin "3") (pinfunction "3_3") (pintype "passive"))
      (node (ref "U2") (pin "13") (pinfunction "PWM7_13") (pintype "output"))
    )
    (net (code "44") (name "SERVO9") (class "Default")
      (node (ref "J11") (pin "3") (pinfunction "3_3") (pintype "passive"))
      (node (ref "U2") (pin "15") (pinfunction "PWM8_15") (pintype "output"))
    )
    (net (code "45") (name "SERVO10") (class "Default")
      (node (ref "J12") (pin "3") (pinfunction "3_3") (pintype "passive"))
      (node (ref "UC1") (pin "19") (pinfunction "PB1/ADC12_IN9/TIM3_CH4_19") (pintype "bidirectional"))
    )
    (net (code "46") (name "SERVO11") (class "Default")
      (node (ref "J13") (pin "3") (pinfunction "3_3") (pintype "passive"))
      (node (ref "UC1") (pin "18") (pinfunction "PB0/ADC12_IN8/TIM3_CH3_18") (pintype "bidirectional"))
    )
    (net (code "47") (name "SERVO12") (class "Default")
      (node (ref "J14") (pin "3") (pinfunction "3_3") (pintype "passive"))
      (node (ref "UC1") (pin "17") (pinfunction "PA7/SPI1_MOSI/ADC12_IN7/TIM3_CH2_17") (pintype "bidirectional"))
    )
    (net (code "48") (name "SERVO13") (class "Default")
      (node (ref "J15") (pin "3") (pinfunction "3_3") (pintype "passive"))
      (node (ref "UC1") (pin "16") (pinfunction "PA6/SPI1_MISO/ADC12_IN6/TIM3_CH1_16") (pintype "bidirectional"))
    )
    (net (code "49") (name "SERVO14") (class "Default")
      (node (ref "J16") (pin "3") (pinfunction "3_3") (pintype "passive"))
      (node (ref "U2") (pin "22") (pinfunction "PWM15_22") (pintype "output"))
    )
    (net (code "50") (name "SERVO15") (class "Default")
      (node (ref "J17") (pin "3") (pinfunction "3_3") (pintype "passive"))
      (node (ref "U2") (pin "21") (pinfunction "PWM14_21") (pintype "output"))
    )
    (net (code "51") (name "SERVO16") (class "Default")
      (node (ref "J18") (pin "3") (pinfunction "3_3") (pintype "passive"))
      (node (ref "U2") (pin "20") (pinfunction "PWM13_20") (pintype "output"))
    )
    (net (code "52") (name "SERVO17") (class "Default")
      (node (ref "J19") (pin "3") (pinfunction "3_3") (pintype "passive"))
      (node (ref "U2") (pin "19") (pinfunction "PWM12_19") (pintype "output"))
    )
    (net (code "53") (name "SERVO18") (class "Default")
      (node (ref "J20") (pin "3") (pinfunction "3_3") (pintype "passive"))
      (node (ref "U2") (pin "18") (pinfunction "PWM11_18") (pintype "output"))
    )
    (net (code "54") (name "SERVO19") (class "Default")
      (node (ref "J21") (pin "3") (pinfunction "3_3") (pintype "passive"))
      (node (ref "U2") (pin "17") (pinfunction "PWM10_17") (pintype "output"))
    )
    (net (code "55") (name "SERVO20") (class "Default")
      (node (ref "J22") (pin "3") (pinfunction "3_3") (pintype "passive"))
      (node (ref "U2") (pin "16") (pinfunction "PWM9_16") (pintype "output"))
    )
    (net (code "56") (name "UART1_RX") (class "Default")
      (node (ref "R1") (pin "2") (pinfunction "2_2") (pintype "passive"))
      (node (ref "UC1") (pin "31") (pinfunction "PA10/USART1_RX/TIM1_CH3_31") (pintype "bidirectional"))
    )
    (net (code "57") (name "UART1_TX") (class "Default")
      (node (ref "R2") (pin "2") (pinfunction "2_2") (pintype "passive"))
      (node (ref "UC1") (pin "30") (pinfunction "PA9/USART1_TX/TIM1_CH2_30") (pintype "input"))
    )
    (net (code "58") (name "USBDM") (class "Default")
      (node (ref "C12") (pin "1") (pinfunction "1_1") (pintype "passive"))
      (node (ref "R14") (pin "2") (pinfunction "2_2") (pintype "passive"))
      (node (ref "UC1") (pin "32") (pinfunction "PA11/USART1_CTS/CAN_RX/TIM1_CH4/USBDM_32") (pintype "bidirectional"))
    )
    (net (code "59") (name "USBDP") (class "Default")
      (node (ref "C13") (pin "1") (pinfunction "1_1") (pintype "passive"))
      (node (ref "R13") (pin "2") (pinfunction "2_2") (pintype "passive"))
      (node (ref "R20") (pin "1") (pinfunction "1_1") (pintype "passive"))
      (node (ref "UC1") (pin "33") (pinfunction "PA12/USART1_RTS/CAN_TX/TIM1_ETR/USBDP_33") (pintype "bidirectional"))
    )
    (net (code "60") (name "VBAT_SENS") (class "Default")
      (node (ref "R4") (pin "1") (pinfunction "1_1") (pintype "passive"))
      (node (ref "R5") (pin "2") (pinfunction "2_2") (pintype "passive"))
      (node (ref "UC1") (pin "13") (pinfunction "PA3/USART2_RX/ADC12_IN3/TIM2_CH4_13") (pintype "bidirectional"))
    )
    (net (code "61") (name "V_BATT") (class "Default")
      (node (ref "C5") (pin "+") (pinfunction "+_+") (pintype "passive"))
      (node (ref "D1") (pin "A") (pinfunction "A_A") (pintype "passive"))
      (node (ref "J10") (pin "2") (pinfunction "2_2") (pintype "passive"))
      (node (ref "J11") (pin "2") (pinfunction "2_2") (pintype "passive"))
      (node (ref "J12") (pin "2") (pinfunction "2_2") (pintype "passive"))
      (node (ref "J13") (pin "2") (pinfunction "2_2") (pintype "passive"))
      (node (ref "J14") (pin "2") (pinfunction "2_2") (pintype "passive"))
      (node (ref "J15") (pin "2") (pinfunction "2_2") (pintype "passive"))
      (node (ref "J16") (pin "2") (pinfunction "2_2") (pintype "passive"))
      (node (ref "J17") (pin "2") (pinfunction "2_2") (pintype "passive"))
      (node (ref "J18") (pin "2") (pinfunction "2_2") (pintype "passive"))
      (node (ref "J19") (pin "2") (pinfunction "2_2") (pintype "passive"))
      (node (ref "J20") (pin "2") (pinfunction "2_2") (pintype "passive"))
      (node (ref "J21") (pin "2") (pinfunction "2_2") (pintype "passive"))
      (node (ref "J22") (pin "2") (pinfunction "2_2") (pintype "passive"))
      (node (ref "J3") (pin "2") (pinfunction "2_2") (pintype "passive"))
      (node (ref "J4") (pin "2") (pinfunction "2_2") (pintype "passive"))
      (node (ref "J5") (pin "2") (pinfunction "2_2") (pintype "passive"))
      (node (ref "J6") (pin "2") (pinfunction "2_2") (pintype "passive"))
      (node (ref "J7") (pin "2") (pinfunction "2_2") (pintype "passive"))
      (node (ref "J8") (pin "2") (pinfunction "2_2") (pintype "passive"))
      (node (ref "J9") (pin "2") (pinfunction "2_2") (pintype "passive"))
      (node (ref "Q1") (pin "2") (pinfunction "S_2") (pintype "passive"))
      (node (ref "R4") (pin "2") (pinfunction "2_2") (pintype "passive"))
    )
    (net (code "62") (name "V_USB") (class "Default")
      (node (ref "D3") (pin "A") (pinfunction "A_A") (pintype "passive"))
      (node (ref "F1") (pin "2") (pinfunction "2_2") (pintype "bidirectional"))
    )
    (net (code "63") (name "unconnected-(S1-Pad1)") (class "Default")
      (node (ref "S1") (pin "1") (pinfunction "1_1") (pintype "passive"))
    )
    (net (code "64") (name "unconnected-(S1-Pad3)") (class "Default")
      (node (ref "S1") (pin "3") (pinfunction "3_3") (pintype "passive"))
    )
    (net (code "65") (name "unconnected-(U$2-AUX_CL-Pad7)") (class "Default")
      (node (ref "U$2") (pin "7") (pinfunction "AUX_CL_7") (pintype "bidirectional"))
    )
    (net (code "66") (name "unconnected-(U$2-AUX_DA-Pad6)") (class "Default")
      (node (ref "U$2") (pin "6") (pinfunction "AUX_DA_6") (pintype "bidirectional"))
    )
    (net (code "67") (name "unconnected-(U2-A0-Pad1)") (class "Default")
      (node (ref "U2") (pin "1") (pinfunction "A0_1") (pintype "bidirectional"))
    )
    (net (code "68") (name "unconnected-(U2-A1-Pad2)") (class "Default")
      (node (ref "U2") (pin "2") (pinfunction "A1_2") (pintype "bidirectional"))
    )
    (net (code "69") (name "unconnected-(U2-A2-Pad3)") (class "Default")
      (node (ref "U2") (pin "3") (pinfunction "A2_3") (pintype "bidirectional"))
    )
    (net (code "70") (name "unconnected-(U2-A3-Pad4)") (class "Default")
      (node (ref "U2") (pin "4") (pinfunction "A3_4") (pintype "bidirectional"))
    )
    (net (code "71") (name "unconnected-(U2-A4-Pad5)") (class "Default")
      (node (ref "U2") (pin "5") (pinfunction "A4_5") (pintype "bidirectional"))
    )
    (net (code "72") (name "unconnected-(U2-A5-Pad24)") (class "Default")
      (node (ref "U2") (pin "24") (pinfunction "A5_24") (pintype "bidirectional"))
    )
    (net (code "73") (name "unconnected-(U3-BP-Pad4)") (class "Default")
      (node (ref "U3") (pin "4") (pinfunction "BP_4") (pintype "input"))
    )
    (net (code "74") (name "unconnected-(UC1-PA0_WKUP{slash}USART2_CTS{slash}ADC12_IN0{slash}TIM2_CH1_ETR-Pad10)") (class "Default")
      (node (ref "UC1") (pin "10") (pinfunction "PA0_WKUP/USART2_CTS/ADC12_IN0/TIM2_CH1_ETR_10") (pintype "bidirectional"))
    )
    (net (code "75") (name "unconnected-(UC1-PA1{slash}USART2_RTS{slash}ADC12_IN1{slash}TIM2_CH2-Pad11)") (class "Default")
      (node (ref "UC1") (pin "11") (pinfunction "PA1/USART2_RTS/ADC12_IN1/TIM2_CH2_11") (pintype "bidirectional"))
    )
    (net (code "76") (name "unconnected-(UC1-PA2{slash}USART2_TX{slash}ADC12_IN2{slash}TIM2_CH3-Pad12)") (class "Default")
      (node (ref "UC1") (pin "12") (pinfunction "PA2/USART2_TX/ADC12_IN2/TIM2_CH3_12") (pintype "bidirectional"))
    )
    (net (code "77") (name "unconnected-(UC1-PA4{slash}SPI1_NSS{slash}USART2_CK{slash}ADC12_IN4-Pad14)") (class "Default")
      (node (ref "UC1") (pin "14") (pinfunction "PA4/SPI1_NSS/USART2_CK/ADC12_IN4_14") (pintype "bidirectional"))
    )
    (net (code "78") (name "unconnected-(UC1-PA8{slash}USART1_CK{slash}TIM1_CH1{slash}MCO-Pad29)") (class "Default")
      (node (ref "UC1") (pin "29") (pinfunction "PA8/USART1_CK/TIM1_CH1/MCO_29") (pintype "bidirectional"))
    )
    (net (code "79") (name "unconnected-(UC1-PA13{slash}JTMS{slash}SWDIO-Pad34)") (class "Default")
      (node (ref "UC1") (pin "34") (pinfunction "PA13/JTMS/SWDIO_34") (pintype "bidirectional"))
    )
    (net (code "80") (name "unconnected-(UC1-PA14{slash}JTCK{slash}SWCLK-Pad37)") (class "Default")
      (node (ref "UC1") (pin "37") (pinfunction "PA14/JTCK/SWCLK_37") (pintype "bidirectional"))
    )
    (net (code "81") (name "unconnected-(UC1-PA15{slash}JTDI-Pad38)") (class "Default")
      (node (ref "UC1") (pin "38") (pinfunction "PA15/JTDI_38") (pintype "bidirectional"))
    )
    (net (code "82") (name "unconnected-(UC1-PB3{slash}JTDO-Pad39)") (class "Default")
      (node (ref "UC1") (pin "39") (pinfunction "PB3/JTDO_39") (pintype "bidirectional"))
    )
    (net (code "83") (name "unconnected-(UC1-PB4{slash}NJTRST-Pad40)") (class "Default")
      (node (ref "UC1") (pin "40") (pinfunction "PB4/NJTRST_40") (pintype "bidirectional"))
    )
    (net (code "84") (name "unconnected-(UC1-PB9{slash}TIM4_CH4-Pad46)") (class "Default")
      (node (ref "UC1") (pin "46") (pinfunction "PB9/TIM4_CH4_46") (pintype "input"))
    )
    (net (code "85") (name "unconnected-(UC1-PB12{slash}SPI2_NSS{slash}I2C2_SMBA{slash}USART3_CK{slash}TIM1_BKIN-Pad25)") (class "Default")
      (node (ref "UC1") (pin "25") (pinfunction "PB12/SPI2_NSS/I2C2_SMBA/USART3_CK/TIM1_BKIN_25") (pintype "input"))
    )
    (net (code "86") (name "unconnected-(UC1-PB13{slash}SPI2_SCK{slash}USART3_CTS{slash}TIM1_CH1N-Pad26)") (class "Default")
      (node (ref "UC1") (pin "26") (pinfunction "PB13/SPI2_SCK/USART3_CTS/TIM1_CH1N_26") (pintype "input"))
    )
    (net (code "87") (name "unconnected-(UC1-PB14{slash}SPI2_MISO{slash}USART3_RTS{slash}TIM1_CH2N-Pad27)") (class "Default")
      (node (ref "UC1") (pin "27") (pinfunction "PB14/SPI2_MISO/USART3_RTS/TIM1_CH2N_27") (pintype "input"))
    )
    (net (code "88") (name "unconnected-(UC1-PB15{slash}SPI2_MOSI{slash}TIM1_CH3N-Pad28)") (class "Default")
      (node (ref "UC1") (pin "28") (pinfunction "PB15/SPI2_MOSI/TIM1_CH3N_28") (pintype "input"))
    )
    (net (code "89") (name "unconnected-(UC1-PC13-TAMPER-RTC-Pad2)") (class "Default")
      (node (ref "UC1") (pin "2") (pinfunction "PC13-TAMPER-RTC_2") (pintype "input"))
    )
    (net (code "90") (name "unconnected-(UC1-PC14-OSC32_IN-Pad3)") (class "Default")
      (node (ref "UC1") (pin "3") (pinfunction "PC14-OSC32_IN_3") (pintype "input"))
    )
    (net (code "91") (name "unconnected-(UC1-PC15-OSC32_OUT-Pad4)") (class "Default")
      (node (ref "UC1") (pin "4") (pinfunction "PC15-OSC32_OUT_4") (pintype "input"))
    )
  )
)
